# ArduinoNano.net
KiCad netlist of a schematic drawn in Altium Designer
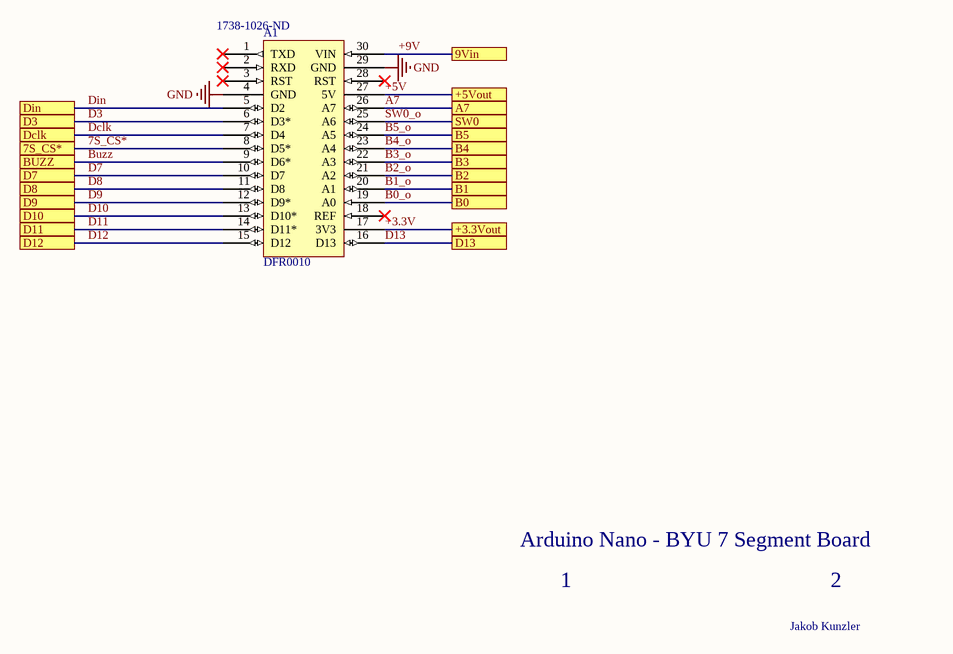
[diagram p0: ArduinoNano.SchDoc]

(export (version "E")
  (design (tool "Eeschema 10.0.6"))
  (components
    (comp (ref "A1")
      (value "DFR0010")
      (footprint "ArduinoNano")
      (description "DFRDUINO NANO V3.1 (ARDUINO NANO")
      (fields (field (name "SUPPLIER PART NUMBER 1") "1738-1026-ND"))
      (libsource (lib "BYU7SegBoard") (part "ArduinoNano"))
    )
  )
  (nets
    (net (code "1") (name "/+3.3V") (class "Default")
      (node (ref "A1") (pin "17") (pinfunction "3V3_17") (pintype "power_in"))
    )
    (net (code "2") (name "/+5V") (class "Default")
      (node (ref "A1") (pin "27") (pinfunction "5V_27") (pintype "power_in"))
    )
    (net (code "3") (name "/+9V") (class "Default")
      (node (ref "A1") (pin "30") (pinfunction "VIN_30") (pintype "input"))
    )
    (net (code "4") (name "/7S_CS*") (class "Default")
      (node (ref "A1") (pin "8") (pinfunction "D5*_8") (pintype "bidirectional"))
    )
    (net (code "5") (name "/A7") (class "Default")
      (node (ref "A1") (pin "26") (pinfunction "A7_26") (pintype "bidirectional"))
    )
    (net (code "6") (name "/B0_o") (class "Default")
      (node (ref "A1") (pin "19") (pinfunction "A0_19") (pintype "input"))
    )
    (net (code "7") (name "/B1_o") (class "Default")
      (node (ref "A1") (pin "20") (pinfunction "A1_20") (pintype "bidirectional"))
    )
    (net (code "8") (name "/B2_o") (class "Default")
      (node (ref "A1") (pin "21") (pinfunction "A2_21") (pintype "bidirectional"))
    )
    (net (code "9") (name "/B3_o") (class "Default")
      (node (ref "A1") (pin "22") (pinfunction "A3_22") (pintype "bidirectional"))
    )
    (net (code "10") (name "/B4_o") (class "Default")
      (node (ref "A1") (pin "23") (pinfunction "A4_23") (pintype "bidirectional"))
    )
    (net (code "11") (name "/B5_o") (class "Default")
      (node (ref "A1") (pin "24") (pinfunction "A5_24") (pintype "bidirectional"))
    )
    (net (code "12") (name "/Buzz") (class "Default")
      (node (ref "A1") (pin "9") (pinfunction "D6*_9") (pintype "bidirectional"))
    )
    (net (code "13") (name "/D3") (class "Default")
      (node (ref "A1") (pin "6") (pinfunction "D3*_6") (pintype "bidirectional"))
    )
    (net (code "14") (name "/D7") (class "Default")
      (node (ref "A1") (pin "10") (pinfunction "D7_10") (pintype "bidirectional"))
    )
    (net (code "15") (name "/D8") (class "Default")
      (node (ref "A1") (pin "11") (pinfunction "D8_11") (pintype "bidirectional"))
    )
    (net (code "16") (name "/D9") (class "Default")
      (node (ref "A1") (pin "12") (pinfunction "D9*_12") (pintype "bidirectional"))
    )
    (net (code "17") (name "/D10") (class "Default")
      (node (ref "A1") (pin "13") (pinfunction "D10*_13") (pintype "bidirectional"))
    )
    (net (code "18") (name "/D11") (class "Default")
      (node (ref "A1") (pin "14") (pinfunction "D11*_14") (pintype "bidirectional"))
    )
    (net (code "19") (name "/D12") (class "Default")
      (node (ref "A1") (pin "15") (pinfunction "D12_15") (pintype "bidirectional"))
    )
    (net (code "20") (name "/D13") (class "Default")
      (node (ref "A1") (pin "16") (pinfunction "D13_16") (pintype "bidirectional"))
    )
    (net (code "21") (name "/Dclk") (class "Default")
      (node (ref "A1") (pin "7") (pinfunction "D4_7") (pintype "bidirectional"))
    )
    (net (code "22") (name "/Din") (class "Default")
      (node (ref "A1") (pin "5") (pinfunction "D2_5") (pintype "bidirectional"))
    )
    (net (code "23") (name "/SW0_o") (class "Default")
      (node (ref "A1") (pin "25") (pinfunction "A6_25") (pintype "bidirectional"))
    )
    (net (code "24") (name "GND") (class "Default")
      (node (ref "A1") (pin "29") (pinfunction "GND_29") (pintype "passive"))
      (node (ref "A1") (pin "4") (pinfunction "GND_4") (pintype "passive"))
    )
    (net (code "25") (name "unconnected-(A1-REF-Pad18)") (class "Default")
      (node (ref "A1") (pin "18") (pinfunction "REF_18") (pintype "input+no_connect"))
    )
    (net (code "26") (name "unconnected-(A1-RST-Pad3)") (class "Default")
      (node (ref "A1") (pin "3") (pinfunction "RST_3") (pintype "input+no_connect"))
    )
    (net (code "27") (name "unconnected-(A1-RST-Pad28)") (class "Default")
      (node (ref "A1") (pin "28") (pinfunction "RST_28") (pintype "input+no_connect"))
    )
    (net (code "28") (name "unconnected-(A1-RXD-Pad2)") (class "Default")
      (node (ref "A1") (pin "2") (pinfunction "RXD_2") (pintype "input+no_connect"))
    )
    (net (code "29") (name "unconnected-(A1-TXD-Pad1)") (class "Default")
      (node (ref "A1") (pin "1") (pinfunction "TXD_1") (pintype "output+no_connect"))
    )
  )
)
